# DVT-PowerAMP-Stage.net
KiCad netlist of a schematic drawn in Altium Designer
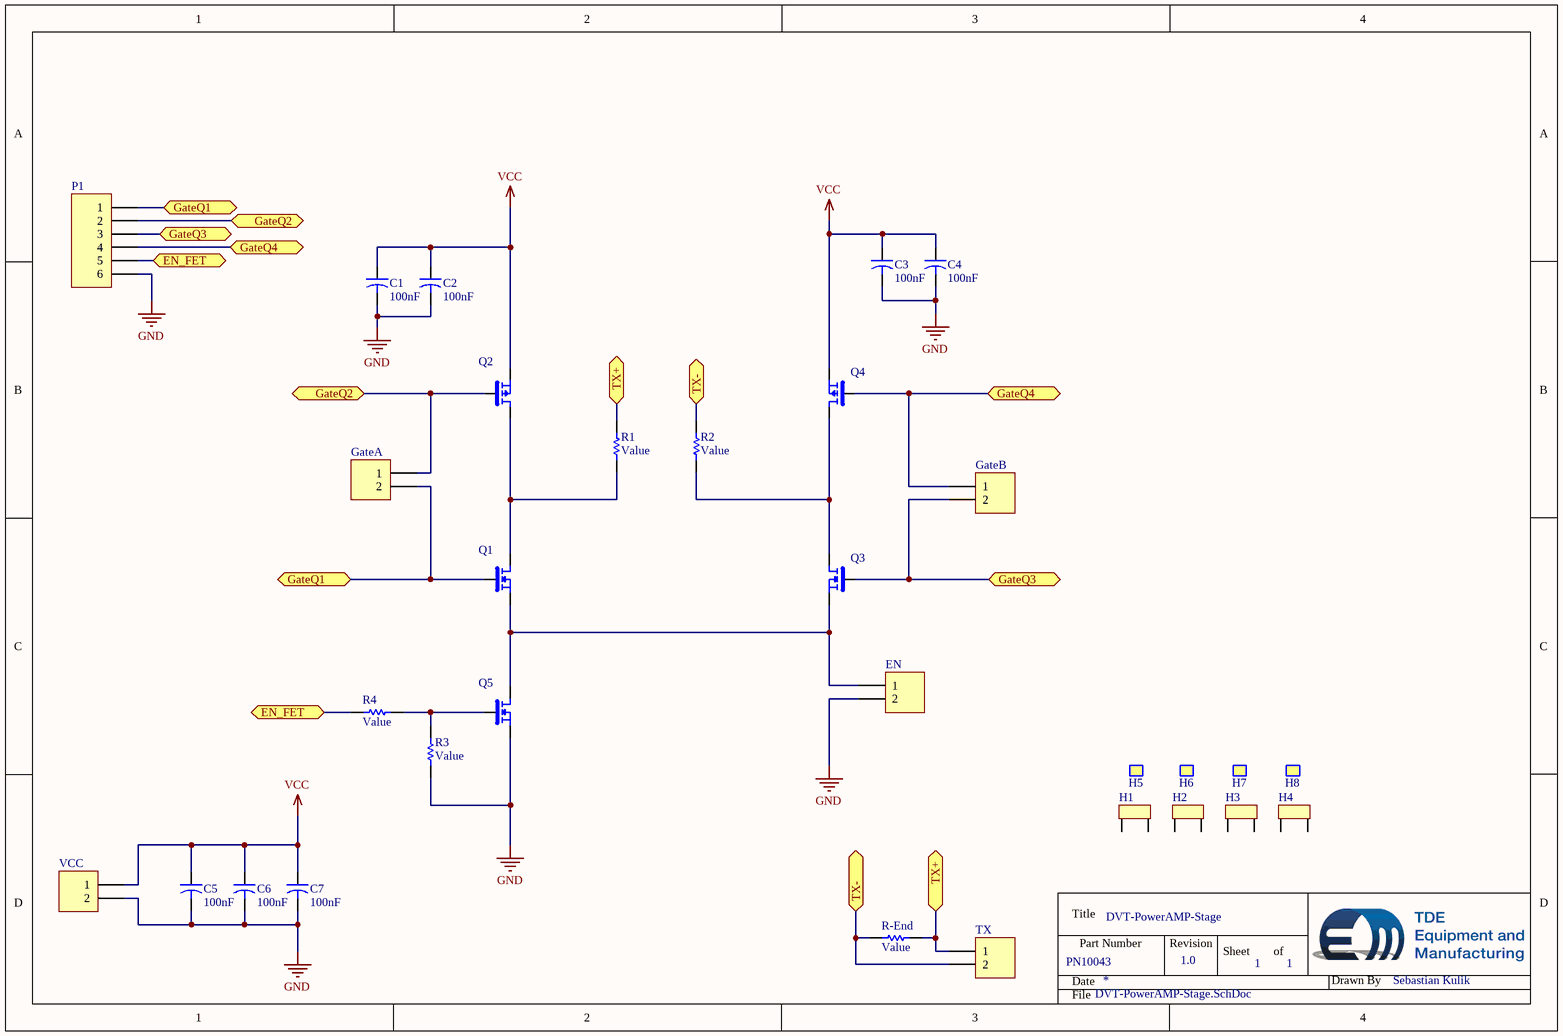
[diagram p0: DVT-PowerAMP-Stage.SchDoc]

(export (version "E")
  (design (tool "Eeschema 10.0.6"))
  (components
    (comp (ref "C1")
      (value "100nF")
      (footprint "Dummy-10mm")
      (description "Capacitor-Dummy-THT")
      (fields (field (name "MANUFACTURER") "AVX") (field (name "PUBLISHER") "Sebastian Kulik"))
      (libsource (lib "Capacitors") (part "Capacitor-Dummy-THT"))
    )
    (comp (ref "C2")
      (value "100nF")
      (footprint "Dummy-10mm")
      (description "Capacitor-Dummy-THT")
      (fields (field (name "MANUFACTURER") "AVX") (field (name "PUBLISHER") "Sebastian Kulik"))
      (libsource (lib "Capacitors") (part "Capacitor-Dummy-THT"))
    )
    (comp (ref "C3")
      (value "100nF")
      (footprint "Dummy-10mm")
      (description "Capacitor-Dummy-THT")
      (fields (field (name "MANUFACTURER") "AVX") (field (name "PUBLISHER") "Sebastian Kulik"))
      (libsource (lib "Capacitors") (part "Capacitor-Dummy-THT"))
    )
    (comp (ref "C4")
      (value "100nF")
      (footprint "Dummy-10mm")
      (description "Capacitor-Dummy-THT")
      (fields (field (name "MANUFACTURER") "AVX") (field (name "PUBLISHER") "Sebastian Kulik"))
      (libsource (lib "Capacitors") (part "Capacitor-Dummy-THT"))
    )
    (comp (ref "C5")
      (value "100nF")
      (footprint "Dummy-10mm")
      (description "Capacitor-Dummy-THT")
      (fields (field (name "MANUFACTURER") "AVX") (field (name "PUBLISHER") "Sebastian Kulik"))
      (libsource (lib "Capacitors") (part "Capacitor-Dummy-THT"))
    )
    (comp (ref "C6")
      (value "100nF")
      (footprint "Dummy-10mm")
      (description "Capacitor-Dummy-THT")
      (fields (field (name "MANUFACTURER") "AVX") (field (name "PUBLISHER") "Sebastian Kulik"))
      (libsource (lib "Capacitors") (part "Capacitor-Dummy-THT"))
    )
    (comp (ref "C7")
      (value "100nF")
      (footprint "Dummy-10mm")
      (description "Capacitor-Dummy-THT")
      (fields (field (name "MANUFACTURER") "AVX") (field (name "PUBLISHER") "Sebastian Kulik"))
      (libsource (lib "Capacitors") (part "Capacitor-Dummy-THT"))
    )
    (comp (ref "EN")
      (value "PHOENIX_1715721")
      (footprint "HDR1X2")
      (description "Plug, 2-Pin")
      (fields (field (name "MANUFACTURER") "WE") (field (name "PUBLISHER") "Sebastian Kulik"))
      (libsource (lib "Connectors") (part "Plug_2_90_2.54"))
    )
    (comp (ref "GateA")
      (value "Plug_2_90_2.54")
      (footprint "HDR1X2")
      (description "Plug, 2-Pin")
      (fields (field (name "MANUFACTURER") "WE") (field (name "PUBLISHER") "Sebastian Kulik"))
      (libsource (lib "") (part "Plug_2_90_2.54_1"))
    )
    (comp (ref "GateB")
      (value "Plug_2_90_2.54")
      (footprint "HDR1X2")
      (description "Plug, 2-Pin")
      (fields (field (name "MANUFACTURER") "WE") (field (name "PUBLISHER") "Sebastian Kulik"))
      (libsource (lib "Connectors") (part "Plug_2_90_2.54"))
    )
    (comp (ref "H1")
      (value "SK129-25,4-STS-220")
      (footprint "SK129-25,4-STS-220")
      (description "Heatsink, 6.5K/W, TO220")
      (fields (field (name "MANUFACTURER") "Fischer Elektronik") (field (name "PUBLISHER") "Sebastian Kulik"))
      (libsource (lib "Discrete") (part "SK129-25,4-STS-220"))
    )
    (comp (ref "H2")
      (value "SK129-25,4-STS-220")
      (footprint "SK129-25,4-STS-220")
      (description "Heatsink, 6.5K/W, TO220")
      (fields (field (name "MANUFACTURER") "Fischer Elektronik") (field (name "PUBLISHER") "Sebastian Kulik"))
      (libsource (lib "Discrete") (part "SK129-25,4-STS-220"))
    )
    (comp (ref "H3")
      (value "SK129-25,4-STS-220")
      (footprint "SK129-25,4-STS-220")
      (description "Heatsink, 6.5K/W, TO220")
      (fields (field (name "MANUFACTURER") "Fischer Elektronik") (field (name "PUBLISHER") "Sebastian Kulik"))
      (libsource (lib "Discrete") (part "SK129-25,4-STS-220"))
    )
    (comp (ref "H4")
      (value "SK129-25,4-STS-220")
      (footprint "SK129-25,4-STS-220")
      (description "Heatsink, 6.5K/W, TO220")
      (fields (field (name "MANUFACTURER") "Fischer Elektronik") (field (name "PUBLISHER") "Sebastian Kulik"))
      (libsource (lib "Discrete") (part "SK129-25,4-STS-220"))
    )
    (comp (ref "H5")
      (value "Fischer-Clamp")
      (fields (field (name "MANUFACTURER") "Fischer Elektronik") (field (name "PUBLISHER") "Sebastian Kulik"))
      (libsource (lib "Mechanical") (part "Fischer-Clamp"))
    )
    (comp (ref "H6")
      (value "Fischer-Clamp")
      (fields (field (name "MANUFACTURER") "Fischer Elektronik") (field (name "PUBLISHER") "Sebastian Kulik"))
      (libsource (lib "Mechanical") (part "Fischer-Clamp"))
    )
    (comp (ref "H7")
      (value "Fischer-Clamp")
      (fields (field (name "MANUFACTURER") "Fischer Elektronik") (field (name "PUBLISHER") "Sebastian Kulik"))
      (libsource (lib "Mechanical") (part "Fischer-Clamp"))
    )
    (comp (ref "H8")
      (value "Fischer-Clamp")
      (fields (field (name "MANUFACTURER") "Fischer Elektronik") (field (name "PUBLISHER") "Sebastian Kulik"))
      (libsource (lib "Mechanical") (part "Fischer-Clamp"))
    )
    (comp (ref "P1")
      (value "Plug_06_2.54")
      (footprint "HDR1X6_2.54")
      (description "Plug, 08-Pin")
      (fields (field (name "MANUFACTURER") "WE") (field (name "PUBLISHER") "Sebastian Kulik"))
      (libsource (lib "Connectors") (part "Plug_06_2.54"))
    )
    (comp (ref "Q1")
      (value "CHT-NMOS4010-TO254-T")
      (footprint "TO254")
      (description "N-FET, 40V@ 10A, Saturn series")
      (fields (field (name "MANUFACTURER") "CISSOID") (field (name "PUBLISHER") "Sebastian Kulik"))
      (libsource (lib "Discrete") (part "CHT-NMOS4010-TO254-T"))
    )
    (comp (ref "Q2")
      (value "CHT-PMOS3008-TO254-T")
      (footprint "TO254")
      (description "P-FET, 30V@ 8A, Venus series")
      (fields (field (name "MANUFACTURER") "CISSOID") (field (name "PUBLISHER") "Sebastian Kulik"))
      (libsource (lib "Discrete") (part "CHT-PMOS3008-TO254-T"))
    )
    (comp (ref "Q3")
      (value "CHT-NMOS4010-TO254-T")
      (footprint "TO254")
      (description "N-FET, 40V@ 10A, Saturn series")
      (fields (field (name "MANUFACTURER") "CISSOID") (field (name "PUBLISHER") "Sebastian Kulik"))
      (libsource (lib "Discrete") (part "CHT-NMOS4010-TO254-T"))
    )
    (comp (ref "Q4")
      (value "CHT-PMOS3008-TO254-T")
      (footprint "TO254")
      (description "P-FET, 30V@ 8A, Venus series")
      (fields (field (name "MANUFACTURER") "CISSOID") (field (name "PUBLISHER") "Sebastian Kulik"))
      (libsource (lib "Discrete") (part "CHT-PMOS3008-TO254-T"))
    )
    (comp (ref "Q5")
      (value "CHT-NMOS4010-TO254-T")
      (footprint "TO254")
      (description "N-FET, 40V@ 10A, Saturn series")
      (fields (field (name "MANUFACTURER") "CISSOID") (field (name "PUBLISHER") "Sebastian Kulik"))
      (libsource (lib "Discrete") (part "CHT-NMOS4010-TO254-T"))
    )
    (comp (ref "R-End")
      (value "Value")
      (footprint "Dummy-10mm")
      (description "Resistor-Dummy-THT")
      (fields (field (name "PUBLISHER") "Sebastian Kulik"))
      (libsource (lib "Resistors") (part "Resistor-Dummy-THT"))
    )
    (comp (ref "R1")
      (value "Value")
      (footprint "Dummy-15mm")
      (description "Resistor-Dummy-THT")
      (fields (field (name "PUBLISHER") "Sebastian Kulik"))
      (libsource (lib "Resistors") (part "Resistor-Dummy-THT"))
    )
    (comp (ref "R2")
      (value "Value")
      (footprint "Dummy-15mm")
      (description "Resistor-Dummy-THT")
      (fields (field (name "PUBLISHER") "Sebastian Kulik"))
      (libsource (lib "Resistors") (part "Resistor-Dummy-THT"))
    )
    (comp (ref "R3")
      (value "Value")
      (footprint "Dummy-10mm")
      (description "Resistor-Dummy-THT")
      (fields (field (name "PUBLISHER") "Sebastian Kulik"))
      (libsource (lib "Resistors") (part "Resistor-Dummy-THT"))
    )
    (comp (ref "R4")
      (value "Value")
      (footprint "Dummy-10mm")
      (description "Resistor-Dummy-THT")
      (fields (field (name "PUBLISHER") "Sebastian Kulik"))
      (libsource (lib "Resistors") (part "Resistor-Dummy-THT"))
    )
    (comp (ref "TX")
      (value "PHOENIX_1715721")
      (footprint "Phoenix-2-5_08")
      (description "Phoenix, 2 pol, 5.08mm, 22A, 715721")
      (fields (field (name "MANUFACTURER") "Phoenix") (field (name "PUBLISHER") "Sebastian Kulik"))
      (libsource (lib "") (part "2Pol_1715721_1"))
    )
    (comp (ref "VCC")
      (value "PHOENIX_1715721")
      (footprint "Phoenix-2-5_08")
      (description "Phoenix, 2 pol, 5.08mm, 22A, 715721")
      (fields (field (name "MANUFACTURER") "Phoenix") (field (name "PUBLISHER") "Sebastian Kulik"))
      (libsource (lib "Connectors") (part "2Pol_1715721"))
    )
  )
  (nets
    (net (code "1") (name "/EN_FET") (class "Default")
      (node (ref "P1") (pin "5") (pinfunction "5_5") (pintype "passive"))
      (node (ref "R4") (pin "2") (pinfunction "2_2") (pintype "passive"))
    )
    (net (code "2") (name "/GateQ1") (class "Default")
      (node (ref "GateA") (pin "2") (pinfunction "2_2") (pintype "passive"))
      (node (ref "P1") (pin "1") (pinfunction "1_1") (pintype "passive"))
      (node (ref "Q1") (pin "Gate") (pinfunction "Gate_Gate") (pintype "passive"))
    )
    (net (code "3") (name "/GateQ2") (class "Default")
      (node (ref "GateA") (pin "1") (pinfunction "1_1") (pintype "passive"))
      (node (ref "P1") (pin "2") (pinfunction "2_2") (pintype "passive"))
      (node (ref "Q2") (pin "Gate") (pinfunction "Gate_Gate") (pintype "passive"))
    )
    (net (code "4") (name "/GateQ3") (class "Default")
      (node (ref "GateB") (pin "2") (pinfunction "2_2") (pintype "passive"))
      (node (ref "P1") (pin "3") (pinfunction "3_3") (pintype "passive"))
      (node (ref "Q3") (pin "Gate") (pinfunction "Gate_Gate") (pintype "passive"))
    )
    (net (code "5") (name "/GateQ4") (class "Default")
      (node (ref "GateB") (pin "1") (pinfunction "1_1") (pintype "passive"))
      (node (ref "P1") (pin "4") (pinfunction "4_4") (pintype "passive"))
      (node (ref "Q4") (pin "Gate") (pinfunction "Gate_Gate") (pintype "passive"))
    )
    (net (code "6") (name "/TX+") (class "Default")
      (node (ref "R-End") (pin "2") (pinfunction "2_2") (pintype "passive"))
      (node (ref "R1") (pin "2") (pinfunction "2_2") (pintype "passive"))
      (node (ref "TX") (pin "1") (pinfunction "1_1") (pintype "passive"))
    )
    (net (code "7") (name "/TX-") (class "Default")
      (node (ref "R-End") (pin "1") (pinfunction "1_1") (pintype "passive"))
      (node (ref "R2") (pin "2") (pinfunction "2_2") (pintype "passive"))
      (node (ref "TX") (pin "2") (pinfunction "2_2") (pintype "passive"))
    )
    (net (code "8") (name "GND") (class "Default")
      (node (ref "C1") (pin "2") (pinfunction "2_2") (pintype "passive"))
      (node (ref "C2") (pin "2") (pinfunction "2_2") (pintype "passive"))
      (node (ref "C3") (pin "2") (pinfunction "2_2") (pintype "passive"))
      (node (ref "C4") (pin "2") (pinfunction "2_2") (pintype "passive"))
      (node (ref "C5") (pin "2") (pinfunction "2_2") (pintype "passive"))
      (node (ref "C6") (pin "2") (pinfunction "2_2") (pintype "passive"))
      (node (ref "C7") (pin "2") (pinfunction "2_2") (pintype "passive"))
      (node (ref "EN") (pin "2") (pinfunction "2_2") (pintype "passive"))
      (node (ref "P1") (pin "6") (pinfunction "6_6") (pintype "passive"))
      (node (ref "Q5") (pin "Source") (pinfunction "Source_Source") (pintype "passive"))
      (node (ref "R3") (pin "1") (pinfunction "1_1") (pintype "passive"))
      (node (ref "VCC") (pin "2") (pinfunction "2_2") (pintype "passive"))
    )
    (net (code "9") (name "Net-(EN-Pad1)") (class "Default")
      (node (ref "EN") (pin "1") (pinfunction "1_1") (pintype "passive"))
      (node (ref "Q1") (pin "Source") (pinfunction "Source_Source") (pintype "passive"))
      (node (ref "Q3") (pin "Source") (pinfunction "Source_Source") (pintype "passive"))
      (node (ref "Q5") (pin "Drain") (pinfunction "Drain_Drain") (pintype "passive"))
    )
    (net (code "10") (name "Net-(Q1-PadDrain)") (class "Default")
      (node (ref "Q1") (pin "Drain") (pinfunction "Drain_Drain") (pintype "passive"))
      (node (ref "Q2") (pin "Drain") (pinfunction "Drain_Drain") (pintype "passive"))
      (node (ref "R1") (pin "1") (pinfunction "1_1") (pintype "passive"))
    )
    (net (code "11") (name "Net-(Q3-PadDrain)") (class "Default")
      (node (ref "Q3") (pin "Drain") (pinfunction "Drain_Drain") (pintype "passive"))
      (node (ref "Q4") (pin "Drain") (pinfunction "Drain_Drain") (pintype "passive"))
      (node (ref "R2") (pin "1") (pinfunction "1_1") (pintype "passive"))
    )
    (net (code "12") (name "Net-(Q5-PadGate)") (class "Default")
      (node (ref "Q5") (pin "Gate") (pinfunction "Gate_Gate") (pintype "passive"))
      (node (ref "R3") (pin "2") (pinfunction "2_2") (pintype "passive"))
      (node (ref "R4") (pin "1") (pinfunction "1_1") (pintype "passive"))
    )
    (net (code "13") (name "VCC") (class "Default")
      (node (ref "C1") (pin "1") (pinfunction "1_1") (pintype "passive"))
      (node (ref "C2") (pin "1") (pinfunction "1_1") (pintype "passive"))
      (node (ref "C3") (pin "1") (pinfunction "1_1") (pintype "passive"))
      (node (ref "C4") (pin "1") (pinfunction "1_1") (pintype "passive"))
      (node (ref "C5") (pin "1") (pinfunction "1_1") (pintype "passive"))
      (node (ref "C6") (pin "1") (pinfunction "1_1") (pintype "passive"))
      (node (ref "C7") (pin "1") (pinfunction "1_1") (pintype "passive"))
      (node (ref "Q2") (pin "Source") (pinfunction "Source_Source") (pintype "passive"))
      (node (ref "Q4") (pin "Source") (pinfunction "Source_Source") (pintype "passive"))
      (node (ref "VCC") (pin "1") (pinfunction "1_1") (pintype "passive"))
    )
    (net (code "14") (name "unconnected-(H1-Pad1)") (class "Default")
      (node (ref "H1") (pin "1") (pinfunction "1_1") (pintype "passive"))
    )
    (net (code "15") (name "unconnected-(H1-Pad2)") (class "Default")
      (node (ref "H1") (pin "2") (pinfunction "2_2") (pintype "passive"))
    )
    (net (code "16") (name "unconnected-(H2-Pad1)") (class "Default")
      (node (ref "H2") (pin "1") (pinfunction "1_1") (pintype "passive"))
    )
    (net (code "17") (name "unconnected-(H2-Pad2)") (class "Default")
      (node (ref "H2") (pin "2") (pinfunction "2_2") (pintype "passive"))
    )
    (net (code "18") (name "unconnected-(H3-Pad1)") (class "Default")
      (node (ref "H3") (pin "1") (pinfunction "1_1") (pintype "passive"))
    )
    (net (code "19") (name "unconnected-(H3-Pad2)") (class "Default")
      (node (ref "H3") (pin "2") (pinfunction "2_2") (pintype "passive"))
    )
    (net (code "20") (name "unconnected-(H4-Pad1)") (class "Default")
      (node (ref "H4") (pin "1") (pinfunction "1_1") (pintype "passive"))
    )
    (net (code "21") (name "unconnected-(H4-Pad2)") (class "Default")
      (node (ref "H4") (pin "2") (pinfunction "2_2") (pintype "passive"))
    )
  )
)
